# Smartwatch-PPG-Module.net
KiCad netlist of a schematic drawn in EAGLE
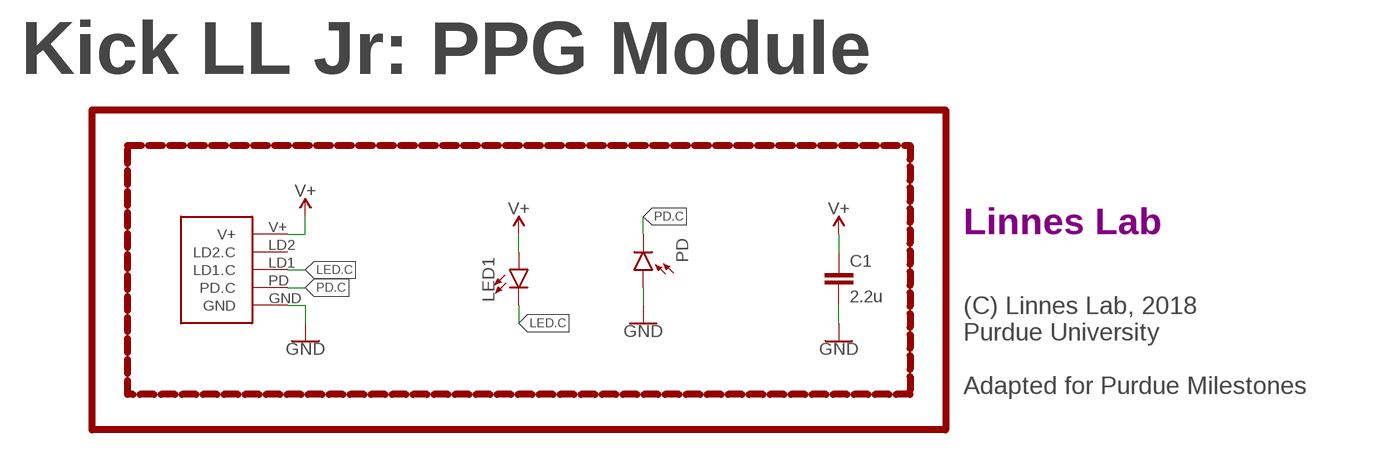
[diagram p0: schematic, sheet 1]

(export (version "E")
  (design (tool "Eeschema 10.0.6"))
  (components
    (comp (ref "C1")
      (value "2.2u")
      (footprint "eagle-import:C0603")
      (libsource (lib "eagle-import") (part "CAPACITOR0603"))
    )
    (comp (ref "J1")
      (value "PPG.MODULE.2")
      (footprint "eagle-import:PPG.MODULE.2")
      (libsource (lib "eagle-import") (part "PPG.MODULE.2"))
    )
    (comp (ref "LED1")
      (value "LED0805")
      (footprint "eagle-import:LED-0805")
      (libsource (lib "eagle-import") (part "LED0805"))
    )
    (comp (ref "PD")
      (value "PHOTODIODE.-SMD.GULLWING")
      (footprint "eagle-import:2-SMD.GULLWING")
      (libsource (lib "eagle-import") (part "PHOTODIODE.-SMD.GULLWING"))
    )
    (comp (ref "U$3")
      (value "LINNES.LAB.LOGO")
      (footprint "eagle-import:LINNES.LAB.LOGO")
      (libsource (lib "eagle-import") (part "LINNES.LAB.LOGO"))
    )
  )
  (nets
    (net (code "1") (name "GND") (class "Default")
      (node (ref "C1") (pin "2") (pinfunction "2_2") (pintype "passive"))
      (node (ref "J1") (pin "GND") (pinfunction "GND_GND") (pintype "bidirectional"))
      (node (ref "PD") (pin "+") (pinfunction "A_+") (pintype "passive"))
    )
    (net (code "2") (name "LED.C") (class "Default")
      (node (ref "J1") (pin "LD1") (pinfunction "LD1.C_LD1") (pintype "bidirectional"))
      (node (ref "LED1") (pin "C") (pinfunction "C_C") (pintype "passive"))
    )
    (net (code "3") (name "PD.C") (class "Default")
      (node (ref "J1") (pin "PD") (pinfunction "PD.C_PD") (pintype "bidirectional"))
      (node (ref "PD") (pin "-") (pinfunction "C_-") (pintype "passive"))
    )
    (net (code "4") (name "V+") (class "Default")
      (node (ref "C1") (pin "1") (pinfunction "1_1") (pintype "passive"))
      (node (ref "J1") (pin "V+") (pinfunction "V+_V+") (pintype "bidirectional"))
      (node (ref "LED1") (pin "A") (pinfunction "A_A") (pintype "passive"))
    )
    (net (code "5") (name "unconnected-(J1-LD2.C-PadLD2)") (class "Default")
      (node (ref "J1") (pin "LD2") (pinfunction "LD2.C_LD2") (pintype "bidirectional"))
    )
  )
)
